# Page05_DDR4L_eMMC.net
KiCad netlist of a schematic drawn in Altium Designer
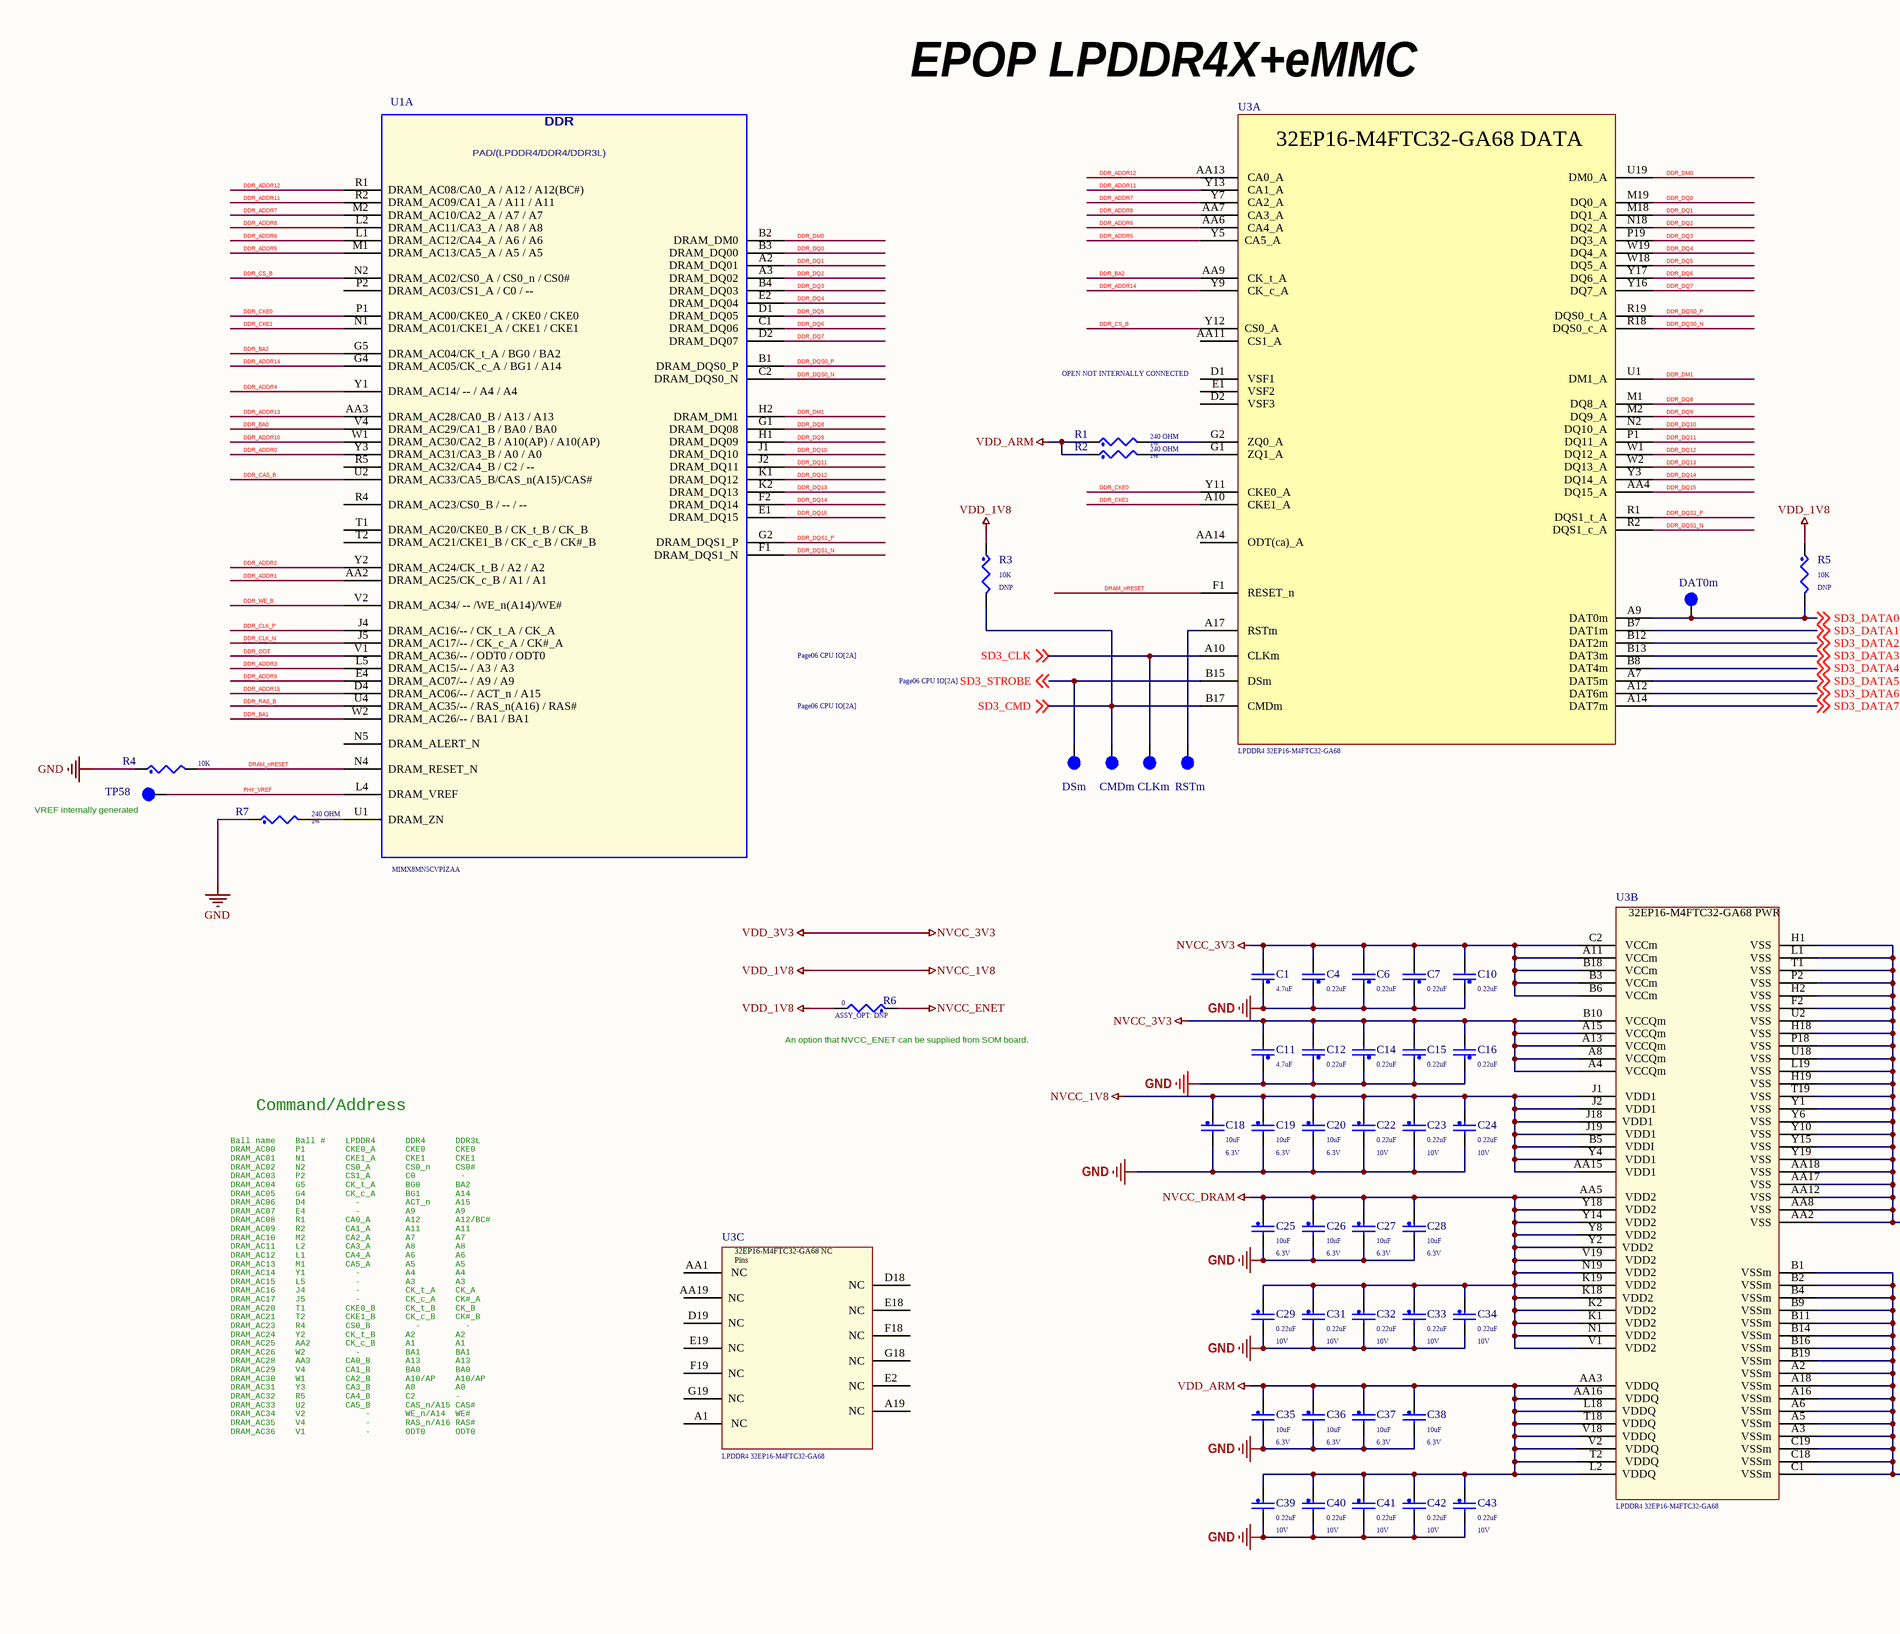
[diagram p0: Page05 DDR4L+eMMC.SchDoc, left]
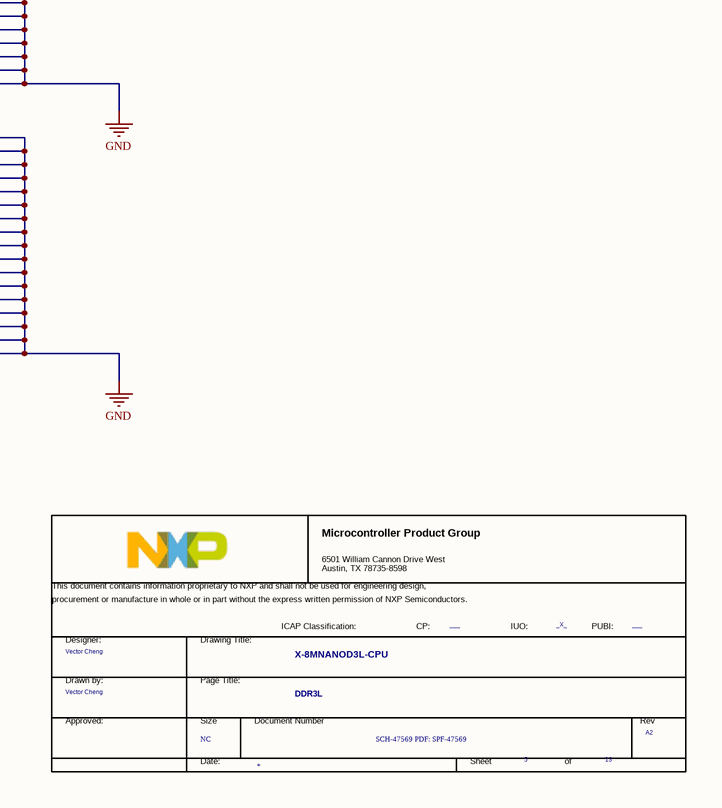
[diagram p1: Page05 DDR4L+eMMC.SchDoc, right]

(export (version "E")
  (design (tool "Eeschema 10.0.6"))
  (components
    (comp (ref "*")
      (value "TitleBlock_MCPG")
      (fields
        (field (name "FCP") "___")
        (field (name "FIUO") "_X_")
        (field (name "PUBI") "___")
        (field (name "DRAWNBY") "Vector Cheng")
        (field (name "DESIGNER") "Vector Cheng")
        (field (name "PAGETITLE") "DDR3L")
        (field (name "PAGE COUNT") "13")
        (field (name "PAGE NUMBER") "5")
        (field (name "PAGE SIZE") "NC")
        (field (name "TITLE") "X-8MNANOD3L-CPU")
        (field (name "REVCODE") "A2")
        (field (name "DOC") "SCH-47569 PDF: SPF-47569")
      )
      (libsource (lib "*") (part "TitleBlock_MCPG"))
    )
    (comp (ref "C1") (value "4.7uF") (footprint "0402_CC - C") (libsource (lib "AA_iMX8_M_") (part "CAP_NP")))
    (comp (ref "C4")
      (value "0.22uF")
      (footprint "0201_CC - C")
      (libsource (lib "AA_iMX8_M_") (part "CAP_NP"))
    )
    (comp (ref "C6")
      (value "0.22uF")
      (footprint "0201_CC - C")
      (libsource (lib "AA_iMX8_M_") (part "CAP_NP"))
    )
    (comp (ref "C7")
      (value "0.22uF")
      (footprint "0201_CC - C")
      (libsource (lib "AA_iMX8_M_") (part "CAP_NP"))
    )
    (comp (ref "C10")
      (value "0.22uF")
      (footprint "0201_CC - C")
      (libsource (lib "AA_iMX8_M_") (part "CAP_NP"))
    )
    (comp (ref "C11")
      (value "4.7uF")
      (footprint "0402_CC - C")
      (libsource (lib "AA_iMX8_M_") (part "CAP_NP"))
    )
    (comp (ref "C12")
      (value "0.22uF")
      (footprint "0201_CC - C")
      (libsource (lib "AA_iMX8_M_") (part "CAP_NP"))
    )
    (comp (ref "C14")
      (value "0.22uF")
      (footprint "0201_CC - C")
      (libsource (lib "AA_iMX8_M_") (part "CAP_NP"))
    )
    (comp (ref "C15")
      (value "0.22uF")
      (footprint "0201_CC - C")
      (libsource (lib "AA_iMX8_M_") (part "CAP_NP"))
    )
    (comp (ref "C16")
      (value "0.22uF")
      (footprint "0201_CC - C")
      (libsource (lib "AA_iMX8_M_") (part "CAP_NP"))
    )
    (comp (ref "C18")
      (value "10uF")
      (footprint "0402_CC - C")
      (fields (field (name "VOLTAGE") "6.3V"))
      (libsource (lib "AA_iMX8_M_") (part "CAP_NP"))
    )
    (comp (ref "C19")
      (value "10uF")
      (footprint "0402_CC - C")
      (fields (field (name "VOLTAGE") "6.3V"))
      (libsource (lib "AA_iMX8_M_") (part "CAP_NP"))
    )
    (comp (ref "C20")
      (value "10uF")
      (footprint "0402_CC - C")
      (fields (field (name "VOLTAGE") "6.3V"))
      (libsource (lib "AA_iMX8_M_") (part "CAP_NP"))
    )
    (comp (ref "C22")
      (value "0.22uF")
      (footprint "0201_CC - C")
      (fields (field (name "VOLTAGE") "10V"))
      (libsource (lib "AA_iMX8_M_") (part "CAP_NP"))
    )
    (comp (ref "C23")
      (value "0.22uF")
      (footprint "0201_CC - C")
      (fields (field (name "VOLTAGE") "10V"))
      (libsource (lib "AA_iMX8_M_") (part "CAP_NP"))
    )
    (comp (ref "C24")
      (value "0.22uF")
      (footprint "0201_CC - C")
      (fields (field (name "VOLTAGE") "10V"))
      (libsource (lib "AA_iMX8_M_") (part "CAP_NP"))
    )
    (comp (ref "C25")
      (value "10uF")
      (footprint "0402_CC - C")
      (fields (field (name "VOLTAGE") "6.3V"))
      (libsource (lib "AA_iMX8_M_") (part "CAP_NP"))
    )
    (comp (ref "C26")
      (value "10uF")
      (footprint "0402_CC - C")
      (fields (field (name "VOLTAGE") "6.3V"))
      (libsource (lib "AA_iMX8_M_") (part "CAP_NP"))
    )
    (comp (ref "C27")
      (value "10uF")
      (footprint "0402_CC - C")
      (fields (field (name "VOLTAGE") "6.3V"))
      (libsource (lib "AA_iMX8_M_") (part "CAP_NP"))
    )
    (comp (ref "C28")
      (value "10uF")
      (footprint "0402_CC - C")
      (fields (field (name "VOLTAGE") "6.3V"))
      (libsource (lib "AA_iMX8_M_") (part "CAP_NP"))
    )
    (comp (ref "C29")
      (value "0.22uF")
      (footprint "0201_CC - C")
      (fields (field (name "VOLTAGE") "10V"))
      (libsource (lib "AA_iMX8_M_") (part "CAP_NP"))
    )
    (comp (ref "C31")
      (value "0.22uF")
      (footprint "0201_CC - C")
      (fields (field (name "VOLTAGE") "10V"))
      (libsource (lib "AA_iMX8_M_") (part "CAP_NP"))
    )
    (comp (ref "C32")
      (value "0.22uF")
      (footprint "0201_CC - C")
      (fields (field (name "VOLTAGE") "10V"))
      (libsource (lib "AA_iMX8_M_") (part "CAP_NP"))
    )
    (comp (ref "C33")
      (value "0.22uF")
      (footprint "0201_CC - C")
      (fields (field (name "VOLTAGE") "10V"))
      (libsource (lib "AA_iMX8_M_") (part "CAP_NP"))
    )
    (comp (ref "C34")
      (value "0.22uF")
      (footprint "0201_CC - C")
      (fields (field (name "VOLTAGE") "10V"))
      (libsource (lib "AA_iMX8_M_") (part "CAP_NP"))
    )
    (comp (ref "C35")
      (value "10uF")
      (footprint "0402_CC - C")
      (fields (field (name "VOLTAGE") "6.3V"))
      (libsource (lib "AA_iMX8_M_") (part "CAP_NP"))
    )
    (comp (ref "C36")
      (value "10uF")
      (footprint "0402_CC - C")
      (fields (field (name "VOLTAGE") "6.3V"))
      (libsource (lib "AA_iMX8_M_") (part "CAP_NP"))
    )
    (comp (ref "C37")
      (value "10uF")
      (footprint "0402_CC - C")
      (fields (field (name "VOLTAGE") "6.3V"))
      (libsource (lib "AA_iMX8_M_") (part "CAP_NP"))
    )
    (comp (ref "C38")
      (value "10uF")
      (footprint "0402_CC - C")
      (fields (field (name "VOLTAGE") "6.3V"))
      (libsource (lib "AA_iMX8_M_") (part "CAP_NP"))
    )
    (comp (ref "C39")
      (value "0.22uF")
      (footprint "0201_CC - C")
      (fields (field (name "VOLTAGE") "10V"))
      (libsource (lib "AA_iMX8_M_") (part "CAP_NP"))
    )
    (comp (ref "C40")
      (value "0.22uF")
      (footprint "0201_CC - C")
      (fields (field (name "VOLTAGE") "10V"))
      (libsource (lib "AA_iMX8_M_") (part "CAP_NP"))
    )
    (comp (ref "C41")
      (value "0.22uF")
      (footprint "0201_CC - C")
      (fields (field (name "VOLTAGE") "10V"))
      (libsource (lib "AA_iMX8_M_") (part "CAP_NP"))
    )
    (comp (ref "C42")
      (value "0.22uF")
      (footprint "0201_CC - C")
      (fields (field (name "VOLTAGE") "10V"))
      (libsource (lib "AA_iMX8_M_") (part "CAP_NP"))
    )
    (comp (ref "C43")
      (value "0.22uF")
      (footprint "0201_CC - C")
      (fields (field (name "VOLTAGE") "10V"))
      (libsource (lib "AA_iMX8_M_") (part "CAP_NP"))
    )
    (comp (ref "CLKm")
      (value "tpad_020")
      (footprint "Test Pin")
      (description "TEST POINT PAD 0.5MM DIA SMT, NO PART TO ORDER")
      (libsource (lib "*") (part "TESTLOOP"))
    )
    (comp (ref "CMDm")
      (value "TPAD_015")
      (footprint "Test Pin")
      (description "TEST POINT PAD 15MIL DIA SMT, NO PART TO ORDER")
      (libsource (lib "*") (part "TESTLOOP"))
    )
    (comp (ref "DAT0m")
      (value "tpad_020")
      (footprint "Test Pin")
      (description "TEST POINT PAD 0.5MM DIA SMT, NO PART TO ORDER")
      (libsource (lib "*") (part "TESTLOOP"))
    )
    (comp (ref "DSm")
      (value "TPAD_015")
      (footprint "Test Pin")
      (description "TEST POINT PAD 15MIL DIA SMT, NO PART TO ORDER")
      (libsource (lib "*") (part "TESTLOOP"))
    )
    (comp (ref "R1")
      (value "240 OHM")
      (footprint "0201_RES")
      (description "RES MF 240 OHM 1/20W 1% 0201")
      (fields (field (name "VOLTAGE") "25V") (field (name "TOLERANCE") "1%"))
      (libsource (lib "*") (part "RES"))
    )
    (comp (ref "R2")
      (value "240 OHM")
      (footprint "0201_RES")
      (description "RES MF 240 OHM 1/20W 1% 0201")
      (fields (field (name "VOLTAGE") "25V") (field (name "TOLERANCE") "1%"))
      (libsource (lib "*") (part "RES"))
    )
    (comp (ref "R3")
      (value "10K")
      (footprint "0201_RES")
      (description "RES MF 10K 1/20W 5% 0201")
      (fields (field (name "ASSY_OPT") "DNP") (field (name "TOLERANCE") "5%"))
      (libsource (lib "*") (part "RES"))
    )
    (comp (ref "R4")
      (value "10K")
      (footprint "0201_RES")
      (description "RES MF 10K 1/20W 5% 0201")
      (fields (field (name "TOLERANCE") "5%"))
      (libsource (lib "*") (part "RES"))
    )
    (comp (ref "R5")
      (value "10K")
      (footprint "0201_RES")
      (description "RES MF 10K 1/20W 5% 0201")
      (fields (field (name "ASSY_OPT") "DNP") (field (name "TOLERANCE") "5%"))
      (libsource (lib "*") (part "RES"))
    )
    (comp (ref "R6")
      (value "0")
      (footprint "0402_CC_RES")
      (description "RES MF ZERO OHM 1/16W 5% 0402")
      (fields
        (field (name "ASSY_OPT") "DNP")
        (field (name "TOLERANCE") "5%")
        (field (name "VOLTAGE") "1/16W")
      )
      (libsource (lib "*") (part "RES"))
    )
    (comp (ref "R7")
      (value "240 OHM")
      (footprint "0201_RES")
      (description "RES MF 240 OHM 1/20W 1% 0201")
      (fields (field (name "VOLTAGE") "25V") (field (name "TOLERANCE") "1%"))
      (libsource (lib "*") (part "RES"))
    )
    (comp (ref "RSTm")
      (value "tpad_020")
      (footprint "Test Pin")
      (description "TEST POINT PAD 0.5MM DIA SMT, NO PART TO ORDER")
      (libsource (lib "*") (part "TESTLOOP"))
    )
    (comp (ref "TP58")
      (value "tpad_020")
      (footprint "Test Pin")
      (description "TEST POINT PAD 0.5MM DIA SMT, NO PART TO ORDER")
      (libsource (lib "*") (part "TESTLOOP"))
    )
    (comp (ref "U1")
      (value "MIMX8MN5CVPIZAA")
      (footprint "BGA306C50P21X21_1100X1100X101")
      (description "IC CPU QUAD CORTEX A53+M7 1.4GHZ -- BGA306")
      (libsource (lib "*") (part "MIMX8MN"))
    )
    (comp (ref "U3")
      (value "LPDDR4 32EP16-M4FTC32-GA68")
      (footprint "FBGA144C40P19X21_800X950X80")
      (libsource (lib "Altium starter project NANO") (part "LPDDR4 32EP16-M4FTC32-GA68"))
    )
  )
  (nets
    (net (code "1") (name "/DDR_ADDR0") (class "Default")
      (node (ref "U1") (pin "Y3") (pinfunction "DRAM_AC31/CA3_B_/_A0_/_A0_Y3") (pintype "passive"))
    )
    (net (code "2") (name "/DDR_ADDR1") (class "Default")
      (node (ref "U1") (pin "AA2") (pinfunction "DRAM_AC25/CK_c_B_/_A1_/_A1_AA2") (pintype "passive"))
    )
    (net (code "3") (name "/DDR_ADDR2") (class "Default")
      (node (ref "U1") (pin "Y2") (pinfunction "DRAM_AC24/CK_t_B_/_A2_/_A2_Y2") (pintype "passive"))
    )
    (net (code "4") (name "/DDR_ADDR3") (class "Default")
      (node (ref "U1") (pin "L5") (pinfunction "DRAM_AC15/--_/_A3_/_A3_L5") (pintype "passive"))
    )
    (net (code "5") (name "/DDR_ADDR4") (class "Default")
      (node (ref "U1") (pin "Y1") (pinfunction "DRAM_AC14/_--_/_A4_/_A4_Y1") (pintype "passive"))
    )
    (net (code "6") (name "/DDR_ADDR5") (class "Default")
      (node (ref "U1") (pin "M1") (pinfunction "DRAM_AC13/CA5_A_/_A5_/_A5_M1") (pintype "passive"))
      (node (ref "U3") (pin "Y5") (pinfunction "CA5_A_Y5") (pintype "passive"))
    )
    (net (code "7") (name "/DDR_ADDR6") (class "Default")
      (node (ref "U1") (pin "L1") (pinfunction "DRAM_AC12/CA4_A_/_A6_/_A6_L1") (pintype "passive"))
      (node (ref "U3") (pin "AA6") (pinfunction "_CA4_A_AA6") (pintype "passive"))
    )
    (net (code "8") (name "/DDR_ADDR7") (class "Default")
      (node (ref "U1") (pin "M2") (pinfunction "DRAM_AC10/CA2_A_/_A7_/_A7_M2") (pintype "passive"))
      (node (ref "U3") (pin "Y7") (pinfunction "_CA2_A_Y7") (pintype "passive"))
    )
    (net (code "9") (name "/DDR_ADDR8") (class "Default")
      (node (ref "U1") (pin "L2") (pinfunction "DRAM_AC11/CA3_A_/_A8_/_A8_L2") (pintype "passive"))
      (node (ref "U3") (pin "AA7") (pinfunction "_CA3_A_AA7") (pintype "passive"))
    )
    (net (code "10") (name "/DDR_ADDR9") (class "Default")
      (node (ref "U1") (pin "E4") (pinfunction "DRAM_AC07/--_/_A9_/_A9_E4") (pintype "passive"))
    )
    (net (code "11") (name "/DDR_ADDR10") (class "Default")
      (node (ref "U1") (pin "W1") (pinfunction "DRAM_AC30/CA2_B_/_A10(AP)_/_A10(AP)_W1") (pintype "passive"))
    )
    (net (code "12") (name "/DDR_ADDR11") (class "Default")
      (node (ref "U1") (pin "R2") (pinfunction "DRAM_AC09/CA1_A_/_A11_/_A11_R2") (pintype "passive"))
      (node (ref "U3") (pin "Y13") (pinfunction "_CA1_A_Y13") (pintype "passive"))
    )
    (net (code "13") (name "/DDR_ADDR12") (class "Default")
      (node (ref "U1") (pin "R1") (pinfunction "DRAM_AC08/CA0_A_/_A12_/_A12(BC#)_R1") (pintype "passive"))
      (node (ref "U3") (pin "AA13") (pinfunction "_CA0_A_AA13") (pintype "passive"))
    )
    (net (code "14") (name "/DDR_ADDR13") (class "Default")
      (node (ref "U1") (pin "AA3") (pinfunction "DRAM_AC28/CA0_B_/_A13_/_A13_AA3") (pintype "passive"))
    )
    (net (code "15") (name "/DDR_ADDR14") (class "Default")
      (node (ref "U1") (pin "G4") (pinfunction "DRAM_AC05/CK_c_A_/_BG1_/_A14_G4") (pintype "passive"))
      (node (ref "U3") (pin "Y9") (pinfunction "_CK_c_A_Y9") (pintype "passive"))
    )
    (net (code "16") (name "/DDR_ADDR15") (class "Default")
      (node (ref "U1") (pin "D4") (pinfunction "DRAM_AC06/--_/_ACT_n_/_A15_D4") (pintype "passive"))
    )
    (net (code "17") (name "/DDR_BA0") (class "Default")
      (node (ref "U1") (pin "V4") (pinfunction "DRAM_AC29/CA1_B_/_BA0_/_BA0_V4") (pintype "passive"))
    )
    (net (code "18") (name "/DDR_BA1") (class "Default")
      (node (ref "U1") (pin "W2") (pinfunction "DRAM_AC26/--_/_BA1_/_BA1_W2") (pintype "passive"))
    )
    (net (code "19") (name "/DDR_BA2") (class "Default")
      (node (ref "U1") (pin "G5") (pinfunction "DRAM_AC04/CK_t_A_/_BG0_/_BA2_G5") (pintype "passive"))
      (node (ref "U3") (pin "AA9") (pinfunction "_CK_t_A_AA9") (pintype "passive"))
    )
    (net (code "20") (name "/DDR_CAS_B") (class "Default")
      (node (ref "U1") (pin "U2") (pinfunction "DRAM_AC33/CA5_B/CAS_n(A15)/CAS#_U2") (pintype "passive"))
    )
    (net (code "21") (name "/DDR_CKE0") (class "Default")
      (node (ref "U1") (pin "P1") (pinfunction "DRAM_AC00/CKE0_A_/_CKE0_/_CKE0_P1") (pintype "passive"))
      (node (ref "U3") (pin "Y11") (pinfunction "_CKE0_A_Y11") (pintype "passive"))
    )
    (net (code "22") (name "/DDR_CKE1") (class "Default")
      (node (ref "U1") (pin "N1") (pinfunction "DRAM_AC01/CKE1_A_/_CKE1_/_CKE1_N1") (pintype "passive"))
      (node (ref "U3") (pin "A10") (pinfunction "_CKE1_A_A10") (pintype "passive"))
    )
    (net (code "23") (name "/DDR_CLK_N") (class "Default")
      (node (ref "U1") (pin "J5") (pinfunction "DRAM_AC17/--_/_CK_c_A_/_CK#_A_J5") (pintype "passive"))
    )
    (net (code "24") (name "/DDR_CLK_P") (class "Default")
      (node (ref "U1") (pin "J4") (pinfunction "DRAM_AC16/--_/_CK_t_A_/_CK_A_J4") (pintype "passive"))
    )
    (net (code "25") (name "/DDR_CS_B") (class "Default")
      (node (ref "U1") (pin "N2") (pinfunction "DRAM_AC02/CS0_A_/_CS0_n_/_CS0#_N2") (pintype "passive"))
      (node (ref "U3") (pin "Y12") (pinfunction "CS0_A_Y12") (pintype "passive"))
    )
    (net (code "26") (name "/DDR_DM0") (class "Default")
      (node (ref "U1") (pin "B2") (pinfunction "DRAM_DM0_B2") (pintype "passive"))
      (node (ref "U3") (pin "U19") (pinfunction "_DM0_A_U19") (pintype "passive"))
    )
    (net (code "27") (name "/DDR_DM1") (class "Default")
      (node (ref "U1") (pin "H2") (pinfunction "DRAM_DM1_H2") (pintype "passive"))
      (node (ref "U3") (pin "U1") (pinfunction "_DM1_A_U1") (pintype "passive"))
    )
    (net (code "28") (name "/DDR_DQ0") (class "Default")
      (node (ref "U1") (pin "B3") (pinfunction "DRAM_DQ00_B3") (pintype "passive"))
      (node (ref "U3") (pin "M19") (pinfunction "_DQ0_A_M19") (pintype "passive"))
    )
    (net (code "29") (name "/DDR_DQ1") (class "Default")
      (node (ref "U1") (pin "A2") (pinfunction "DRAM_DQ01_A2") (pintype "passive"))
      (node (ref "U3") (pin "M18") (pinfunction "DQ1_A_M18") (pintype "passive"))
    )
    (net (code "30") (name "/DDR_DQ2") (class "Default")
      (node (ref "U1") (pin "A3") (pinfunction "DRAM_DQ02_A3") (pintype "passive"))
      (node (ref "U3") (pin "N18") (pinfunction "DQ2_A_N18") (pintype "passive"))
    )
    (net (code "31") (name "/DDR_DQ3") (class "Default")
      (node (ref "U1") (pin "B4") (pinfunction "DRAM_DQ03_B4") (pintype "passive"))
      (node (ref "U3") (pin "P19") (pinfunction "DQ3_A_P19") (pintype "passive"))
    )
    (net (code "32") (name "/DDR_DQ4") (class "Default")
      (node (ref "U1") (pin "E2") (pinfunction "DRAM_DQ04_E2") (pintype "passive"))
      (node (ref "U3") (pin "W19") (pinfunction "_DQ4_A_W19") (pintype "passive"))
    )
    (net (code "33") (name "/DDR_DQ5") (class "Default")
      (node (ref "U1") (pin "D1") (pinfunction "DRAM_DQ05_D1") (pintype "passive"))
      (node (ref "U3") (pin "W18") (pinfunction "DQ5_A_W18") (pintype "passive"))
    )
    (net (code "34") (name "/DDR_DQ6") (class "Default")
      (node (ref "U1") (pin "C1") (pinfunction "DRAM_DQ06_C1") (pintype "passive"))
      (node (ref "U3") (pin "Y17") (pinfunction "_DQ6_A_Y17") (pintype "passive"))
    )
    (net (code "35") (name "/DDR_DQ7") (class "Default")
      (node (ref "U1") (pin "D2") (pinfunction "DRAM_DQ07_D2") (pintype "passive"))
      (node (ref "U3") (pin "Y16") (pinfunction "_DQ7_A_Y16") (pintype "passive"))
    )
    (net (code "36") (name "/DDR_DQ8") (class "Default")
      (node (ref "U1") (pin "G1") (pinfunction "DRAM_DQ08_G1") (pintype "passive"))
      (node (ref "U3") (pin "M1") (pinfunction "_DQ8_A_M1") (pintype "passive"))
    )
    (net (code "37") (name "/DDR_DQ9") (class "Default")
      (node (ref "U1") (pin "H1") (pinfunction "DRAM_DQ09_H1") (pintype "passive"))
      (node (ref "U3") (pin "M2") (pinfunction "_DQ9_A_M2") (pintype "passive"))
    )
    (net (code "38") (name "/DDR_DQ10") (class "Default")
      (node (ref "U1") (pin "J1") (pinfunction "DRAM_DQ10_J1") (pintype "passive"))
      (node (ref "U3") (pin "N2") (pinfunction "_DQ10_A_N2") (pintype "passive"))
    )
    (net (code "39") (name "/DDR_DQ11") (class "Default")
      (node (ref "U1") (pin "J2") (pinfunction "DRAM_DQ11_J2") (pintype "passive"))
      (node (ref "U3") (pin "P1") (pinfunction "_DQ11_A_P1") (pintype "passive"))
    )
    (net (code "40") (name "/DDR_DQ12") (class "Default")
      (node (ref "U1") (pin "K1") (pinfunction "DRAM_DQ12_K1") (pintype "passive"))
      (node (ref "U3") (pin "W1") (pinfunction "_DQ12_A_W1") (pintype "passive"))
    )
    (net (code "41") (name "/DDR_DQ13") (class "Default")
      (node (ref "U1") (pin "K2") (pinfunction "DRAM_DQ13_K2") (pintype "passive"))
      (node (ref "U3") (pin "W2") (pinfunction "_DQ13_A_W2") (pintype "passive"))
    )
    (net (code "42") (name "/DDR_DQ14") (class "Default")
      (node (ref "U1") (pin "F2") (pinfunction "DRAM_DQ14_F2") (pintype "passive"))
      (node (ref "U3") (pin "Y3") (pinfunction "_DQ14_A_Y3") (pintype "passive"))
    )
    (net (code "43") (name "/DDR_DQ15") (class "Default")
      (node (ref "U1") (pin "E1") (pinfunction "DRAM_DQ15_E1") (pintype "passive"))
      (node (ref "U3") (pin "AA4") (pinfunction "_DQ15_A_AA4") (pintype "passive"))
    )
    (net (code "44") (name "/DDR_DQS0_N") (class "Default")
      (node (ref "U1") (pin "C2") (pinfunction "DRAM_DQS0_N_C2") (pintype "passive"))
      (node (ref "U3") (pin "R18") (pinfunction "DQS0_c_A_R18") (pintype "passive"))
    )
    (net (code "45") (name "/DDR_DQS0_P") (class "Default")
      (node (ref "U1") (pin "B1") (pinfunction "DRAM_DQS0_P_B1") (pintype "passive"))
      (node (ref "U3") (pin "R19") (pinfunction "_DQS0_t_A_R19") (pintype "passive"))
    )
    (net (code "46") (name "/DDR_DQS1_N") (class "Default")
      (node (ref "U1") (pin "F1") (pinfunction "DRAM_DQS1_N_F1") (pintype "passive"))
      (node (ref "U3") (pin "R2") (pinfunction "_DQS1_c_A_R2") (pintype "passive"))
    )
    (net (code "47") (name "/DDR_DQS1_P") (class "Default")
      (node (ref "U1") (pin "G2") (pinfunction "DRAM_DQS1_P_G2") (pintype "passive"))
      (node (ref "U3") (pin "R1") (pinfunction "_DQS1_t_A_R1") (pintype "passive"))
    )
    (net (code "48") (name "/DDR_ODT") (class "Default")
      (node (ref "U1") (pin "V1") (pinfunction "DRAM_AC36/--_/_ODT0_/_ODT0_V1") (pintype "passive"))
    )
    (net (code "49") (name "/DDR_RAS_B") (class "Default")
      (node (ref "U1") (pin "U4") (pinfunction "DRAM_AC35/--_/_RAS_n(A16)_/_RAS#_U4") (pintype "passive"))
    )
    (net (code "50") (name "/DDR_WE_B") (class "Default")
      (node (ref "U1") (pin "V2") (pinfunction "DRAM_AC34/_--_/WE_n(A14)/WE#_V2") (pintype "passive"))
    )
    (net (code "51") (name "/DRAM_nRESET") (class "Default")
      (node (ref "R4") (pin "2") (pinfunction "2_2") (pintype "passive"))
      (node (ref "U1") (pin "N4") (pinfunction "DRAM_RESET_N_N4") (pintype "passive"))
      (node (ref "U3") (pin "F1") (pinfunction "_RESET_n_F1") (pintype "passive"))
    )
    (net (code "52") (name "/PHY_VREF") (class "Default")
      (node (ref "TP58") (pin "1") (pinfunction "Pin1_1") (pintype "passive"))
      (node (ref "U1") (pin "L4") (pinfunction "DRAM_VREF_L4") (pintype "passive"))
    )
    (net (code "53") (name "GND") (class "Default")
      (node (ref "C1") (pin "1") (pinfunction "1_1") (pintype "passive"))
      (node (ref "C10") (pin "1") (pinfunction "1_1") (pintype "passive"))
      (node (ref "C11") (pin "1") (pinfunction "1_1") (pintype "passive"))
      (node (ref "C12") (pin "1") (pinfunction "1_1") (pintype "passive"))
      (node (ref "C14") (pin "1") (pinfunction "1_1") (pintype "passive"))
      (node (ref "C15") (pin "1") (pinfunction "1_1") (pintype "passive"))
      (node (ref "C16") (pin "1") (pinfunction "1_1") (pintype "passive"))
      (node (ref "C18") (pin "2") (pinfunction "2_2") (pintype "passive"))
      (node (ref "C19") (pin "2") (pinfunction "2_2") (pintype "passive"))
      (node (ref "C20") (pin "2") (pinfunction "2_2") (pintype "passive"))
      (node (ref "C22") (pin "2") (pinfunction "2_2") (pintype "passive"))
      (node (ref "C23") (pin "2") (pinfunction "2_2") (pintype "passive"))
      (node (ref "C24") (pin "2") (pinfunction "2_2") (pintype "passive"))
      (node (ref "C25") (pin "2") (pinfunction "2_2") (pintype "passive"))
      (node (ref "C26") (pin "2") (pinfunction "2_2") (pintype "passive"))
      (node (ref "C27") (pin "2") (pinfunction "2_2") (pintype "passive"))
      (node (ref "C28") (pin "2") (pinfunction "2_2") (pintype "passive"))
      (node (ref "C29") (pin "2") (pinfunction "2_2") (pintype "passive"))
      (node (ref "C31") (pin "2") (pinfunction "2_2") (pintype "passive"))
      (node (ref "C32") (pin "2") (pinfunction "2_2") (pintype "passive"))
      (node (ref "C33") (pin "2") (pinfunction "2_2") (pintype "passive"))
      (node (ref "C34") (pin "2") (pinfunction "2_2") (pintype "passive"))
      (node (ref "C35") (pin "2") (pinfunction "2_2") (pintype "passive"))
      (node (ref "C36") (pin "2") (pinfunction "2_2") (pintype "passive"))
      (node (ref "C37") (pin "2") (pinfunction "2_2") (pintype "passive"))
      (node (ref "C38") (pin "2") (pinfunction "2_2") (pintype "passive"))
      (node (ref "C39") (pin "2") (pinfunction "2_2") (pintype "passive"))
      (node (ref "C4") (pin "1") (pinfunction "1_1") (pintype "passive"))
      (node (ref "C40") (pin "2") (pinfunction "2_2") (pintype "passive"))
      (node (ref "C41") (pin "2") (pinfunction "2_2") (pintype "passive"))
      (node (ref "C42") (pin "2") (pinfunction "2_2") (pintype "passive"))
      (node (ref "C43") (pin "2") (pinfunction "2_2") (pintype "passive"))
      (node (ref "C6") (pin "1") (pinfunction "1_1") (pintype "passive"))
      (node (ref "C7") (pin "1") (pinfunction "1_1") (pintype "passive"))
      (node (ref "R4") (pin "1") (pinfunction "1_1") (pintype "passive"))
      (node (ref "R7") (pin "1") (pinfunction "1_1") (pintype "passive"))
      (node (ref "U3") (pin "A16") (pinfunction "_VSSm_A16") (pintype "power_in"))
      (node (ref "U3") (pin "A18") (pinfunction "_VSSm_A18") (pintype "power_in"))
      (node (ref "U3") (pin "A2") (pinfunction "_VSSm_A2") (pintype "power_in"))
      (node (ref "U3") (pin "A3") (pinfunction "VSSm_A3") (pintype "power_in"))
      (node (ref "U3") (pin "A5") (pinfunction "_VSSm_A5") (pintype "power_in"))
      (node (ref "U3") (pin "A6") (pinfunction "_VSSm_A6") (pintype "power_in"))
      (node (ref "U3") (pin "AA12") (pinfunction "_VSS_AA12") (pintype "power_in"))
      (node (ref "U3") (pin "AA17") (pinfunction "_VSS_AA17") (pintype "power_in"))
      (node (ref "U3") (pin "AA18") (pinfunction "VSS_AA18") (pintype "power_in"))
      (node (ref "U3") (pin "AA2") (pinfunction "VSS_AA2") (pintype "power_in"))
      (node (ref "U3") (pin "AA8") (pinfunction "_VSS_AA8") (pintype "power_in"))
      (node (ref "U3") (pin "B1") (pinfunction "_VSSm_B1") (pintype "power_in"))
      (node (ref "U3") (pin "B11") (pinfunction "_VSSm_B11") (pintype "power_in"))
      (node (ref "U3") (pin "B14") (pinfunction "_VSSm_B14") (pintype "power_in"))
      (node (ref "U3") (pin "B16") (pinfunction "_VSSm_B16") (pintype "power_in"))
      (node (ref "U3") (pin "B19") (pinfunction "_VSSm_B19") (pintype "power_in"))
      (node (ref "U3") (pin "B2") (pinfunction "_VSSm_B2") (pintype "power_in"))
      (node (ref "U3") (pin "B4") (pinfunction "_VSSm_B4") (pintype "power_in"))
      (node (ref "U3") (pin "B9") (pinfunction "_VSSm_B9") (pintype "power_in"))
      (node (ref "U3") (pin "C1") (pinfunction "_VSSm_C1") (pintype "power_in"))
      (node (ref "U3") (pin "C18") (pinfunction "VSSm_C18") (pintype "power_in"))
      (node (ref "U3") (pin "C19") (pinfunction "_VSSm_C19") (pintype "power_in"))
      (node (ref "U3") (pin "F2") (pinfunction "_VSS_F2") (pintype "power_in"))
      (node (ref "U3") (pin "H1") (pinfunction "_VSS_H1") (pintype "power_in"))
      (node (ref "U3") (pin "H18") (pinfunction "VSS_H18") (pintype "power_in"))
      (node (ref "U3") (pin "H19") (pinfunction "VSS_H19") (pintype "power_in"))
      (node (ref "U3") (pin "H2") (pinfunction "VSS_H2") (pintype "power_in"))
      (node (ref "U3") (pin "L1") (pinfunction "_VSS_L1") (pintype "power_in"))
      (node (ref "U3") (pin "L19") (pinfunction "VSS_L19") (pintype "power_in"))
      (node (ref "U3") (pin "P18") (pinfunction "VSS_P18") (pintype "power_in"))
      (node (ref "U3") (pin "P2") (pinfunction "_VSS_P2") (pintype "power_in"))
      (node (ref "U3") (pin "T1") (pinfunction "_VSS_T1") (pintype "power_in"))
      (node (ref "U3") (pin "T19") (pinfunction "VSS_T19") (pintype "power_in"))
      (node (ref "U3") (pin "U18") (pinfunction "VSS_U18") (pintype "power_in"))
      (node (ref "U3") (pin "U2") (pinfunction "_VSS_U2") (pintype "power_in"))
      (node (ref "U3") (pin "Y1") (pinfunction "_VSS_Y1") (pintype "power_in"))
      (node (ref "U3") (pin "Y10") (pinfunction "_VSS_Y10") (pintype "power_in"))
      (node (ref "U3") (pin "Y15") (pinfunction "_VSS_Y15") (pintype "power_in"))
      (node (ref "U3") (pin "Y19") (pinfunction "VSS_Y19") (pintype "power_in"))
      (node (ref "U3") (pin "Y6") (pinfunction "_VSS_Y6") (pintype "power_in"))
    )
    (net (code "54") (name "NVCC_1V8") (class "Default")
      (node (ref "C18") (pin "1") (pinfunction "1_1") (pintype "passive"))
      (node (ref "C19") (pin "1") (pinfunction "1_1") (pintype "passive"))
      (node (ref "C20") (pin "1") (pinfunction "1_1") (pintype "passive"))
      (node (ref "C22") (pin "1") (pinfunction "1_1") (pintype "passive"))
      (node (ref "C23") (pin "1") (pinfunction "1_1") (pintype "passive"))
      (node (ref "C24") (pin "1") (pinfunction "1_1") (pintype "passive"))
      (node (ref "R3") (pin "1") (pinfunction "1_1") (pintype "passive"))
      (node (ref "R5") (pin "1") (pinfunction "1_1") (pintype "passive"))
      (node (ref "R6") (pin "2") (pinfunction "2_2") (pintype "passive"))
      (node (ref "U3") (pin "AA15") (pinfunction "_VDD1_AA15") (pintype "power_in"))
      (node (ref "U3") (pin "B5") (pinfunction "_VDDI_B5") (pintype "power_in"))
      (node (ref "U3") (pin "J1") (pinfunction "_VDD1_J1") (pintype "power_in"))
      (node (ref "U3") (pin "J18") (pinfunction "VDD1_J18") (pintype "power_in"))
      (node (ref "U3") (pin "J19") (pinfunction "_VDD1_J19") (pintype "power_in"))
      (node (ref "U3") (pin "J2") (pinfunction "_VDD1_J2") (pintype "power_in"))
      (node (ref "U3") (pin "Y4") (pinfunction "_VDD1_Y4") (pintype "power_in"))
    )
    (net (code "55") (name "NVCC_3V3") (class "Default")
      (node (ref "C1") (pin "2") (pinfunction "2_2") (pintype "passive"))
      (node (ref "C10") (pin "2") (pinfunction "2_2") (pintype "passive"))
      (node (ref "C11") (pin "2") (pinfunction "2_2") (pintype "passive"))
      (node (ref "C12") (pin "2") (pinfunction "2_2") (pintype "passive"))
      (node (ref "C14") (pin "2") (pinfunction "2_2") (pintype "passive"))
      (node (ref "C15") (pin "2") (pinfunction "2_2") (pintype "passive"))
      (node (ref "C16") (pin "2") (pinfunction "2_2") (pintype "passive"))
      (node (ref "C4") (pin "2") (pinfunction "2_2") (pintype "passive"))
      (node (ref "C6") (pin "2") (pinfunction "2_2") (pintype "passive"))
      (node (ref "C7") (pin "2") (pinfunction "2_2") (pintype "passive"))
      (node (ref "U3") (pin "A11") (pinfunction "_VCCm_A11") (pintype "power_in"))
      (node (ref "U3") (pin "A13") (pinfunction "_VCCQm_A13") (pintype "power_in"))
      (node (ref "U3") (pin "A15") (pinfunction "_VCCQm_A15") (pintype "power_in"))
      (node (ref "U3") (pin "A4") (pinfunction "_VCCQm_A4") (pintype "power_in"))
      (node (ref "U3") (pin "A8") (pinfunction "_VCCQm_A8") (pintype "power_in"))
      (node (ref "U3") (pin "B10") (pinfunction "_VCCQm_B10") (pintype "power_in"))
      (node (ref "U3") (pin "B18") (pinfunction "_VCCm_B18") (pintype "power_in"))
      (node (ref "U3") (pin "B3") (pinfunction "_VCCm_B3") (pintype "power_in"))
      (node (ref "U3") (pin "B6") (pinfunction "_VCCm_B6") (pintype "power_in"))
      (node (ref "U3") (pin "C2") (pinfunction "_VCCm_C2") (pintype "power_in"))
    )
    (net (code "56") (name "NVCC_DRAM") (class "Default")
      (node (ref "C25") (pin "1") (pinfunction "1_1") (pintype "passive"))
      (node (ref "C26") (pin "1") (pinfunction "1_1") (pintype "passive"))
      (node (ref "C27") (pin "1") (pinfunction "1_1") (pintype "passive"))
      (node (ref "C28") (pin "1") (pinfunction "1_1") (pintype "passive"))
      (node (ref "C29") (pin "1") (pinfunction "1_1") (pintype "passive"))
      (node (ref "C31") (pin "1") (pinfunction "1_1") (pintype "passive"))
      (node (ref "C32") (pin "1") (pinfunction "1_1") (pintype "passive"))
      (node (ref "C33") (pin "1") (pinfunction "1_1") (pintype "passive"))
      (node (ref "C34") (pin "1") (pinfunction "1_1") (pintype "passive"))
      (node (ref "U3") (pin "AA5") (pinfunction "_VDD2_AA5") (pintype "power_in"))
      (node (ref "U3") (pin "K1") (pinfunction "_VDD2_K1") (pintype "power_in"))
      (node (ref "U3") (pin "K18") (pinfunction "VDD2_K18") (pintype "power_in"))
      (node (ref "U3") (pin "K19") (pinfunction "_VDD2_K19") (pintype "power_in"))
      (node (ref "U3") (pin "K2") (pinfunction "_VDD2_K2") (pintype "power_in"))
      (node (ref "U3") (pin "N1") (pinfunction "_VDD2_N1") (pintype "power_in"))
      (node (ref "U3") (pin "N19") (pinfunction "_VDD2_N19") (pintype "power_in"))
      (node (ref "U3") (pin "V1") (pinfunction "_VDD2_V1") (pintype "power_in"))
      (node (ref "U3") (pin "V19") (pinfunction "_VDD2_V19") (pintype "power_in"))
      (node (ref "U3") (pin "Y14") (pinfunction "_VDD2_Y14") (pintype "power_in"))
      (node (ref "U3") (pin "Y18") (pinfunction "_VDD2_Y18") (pintype "power_in"))
      (node (ref "U3") (pin "Y2") (pinfunction "VDD2_Y2") (pintype "power_in"))
      (node (ref "U3") (pin "Y8") (pinfunction "_VDD2_Y8") (pintype "power_in"))
    )
    (net (code "57") (name "NVCC_ENET") (class "Default")
      (node (ref "R6") (pin "1") (pinfunction "1_1") (pintype "passive"))
    )
    (net (code "58") (name "Net-(RSTm-Pin1)") (class "Default")
      (node (ref "RSTm") (pin "1") (pinfunction "Pin1_1") (pintype "passive"))
      (node (ref "U3") (pin "A17") (pinfunction "_RSTm_A17") (pintype "passive"))
    )
    (net (code "59") (name "Net-(U1A-DRAM_ZN)") (class "Default")
      (node (ref "R7") (pin "2") (pinfunction "2_2") (pintype "passive"))
      (node (ref "U1") (pin "U1") (pinfunction "DRAM_ZN_U1") (pintype "passive"))
    )
    (net (code "60") (name "Net-(U3A-_ZQ0_A)") (class "Default")
      (node (ref "R1") (pin "2") (pinfunction "2_2") (pintype "passive"))
      (node (ref "U3") (pin "G2") (pinfunction "_ZQ0_A_G2") (pintype "passive"))
    )
    (net (code "61") (name "Net-(U3A-_ZQ1_A)") (class "Default")
      (node (ref "R2") (pin "2") (pinfunction "2_2") (pintype "passive"))
      (node (ref "U3") (pin "G1") (pinfunction "_ZQ1_A_G1") (pintype "passive"))
    )
    (net (code "62") (name "SD3_CLK") (class "Default")
      (node (ref "CLKm") (pin "1") (pinfunction "Pin1_1") (pintype "passive"))
      (node (ref "U3") (pin "A10") (pinfunction "_CLKm_A10") (pintype "passive"))
    )
    (net (code "63") (name "SD3_CMD") (class "Default")
      (node (ref "CMDm") (pin "1") (pinfunction "Pin1_1") (pintype "passive"))
      (node (ref "R3") (pin "2") (pinfunction "2_2") (pintype "passive"))
      (node (ref "U3") (pin "B17") (pinfunction "_CMDm_B17") (pintype "passive"))
    )
    (net (code "64") (name "SD3_DATA0") (class "Default")
      (node (ref "DAT0m") (pin "1") (pinfunction "Pin1_1") (pintype "passive"))
      (node (ref "R5") (pin "2") (pinfunction "2_2") (pintype "passive"))
      (node (ref "U3") (pin "A9") (pinfunction "_DAT0m_A9") (pintype "passive"))
    )
    (net (code "65") (name "SD3_DATA1") (class "Default")
      (node (ref "U3") (pin "B7") (pinfunction "DAT1m_B7") (pintype "passive"))
    )
    (net (code "66") (name "SD3_DATA2") (class "Default")
      (node (ref "U3") (pin "B12") (pinfunction "_DAT2m_B12") (pintype "passive"))
    )
    (net (code "67") (name "SD3_DATA3") (class "Default")
      (node (ref "U3") (pin "B13") (pinfunction "_DAT3m_B13") (pintype "passive"))
    )
    (net (code "68") (name "SD3_DATA4") (class "Default")
      (node (ref "U3") (pin "B8") (pinfunction "_DAT4m_B8") (pintype "passive"))
    )
    (net (code "69") (name "SD3_DATA5") (class "Default")
      (node (ref "U3") (pin "A7") (pinfunction "_DAT5m_A7") (pintype "passive"))
    )
    (net (code "70") (name "SD3_DATA6") (class "Default")
      (node (ref "U3") (pin "A12") (pinfunction "_DAT6m_A12") (pintype "passive"))
    )
    (net (code "71") (name "SD3_DATA7") (class "Default")
      (node (ref "U3") (pin "A14") (pinfunction "_DAT7m_A14") (pintype "passive"))
    )
    (net (code "72") (name "SD3_STROBE") (class "Default")
      (node (ref "DSm") (pin "1") (pinfunction "Pin1_1") (pintype "passive"))
      (node (ref "U3") (pin "B15") (pinfunction "_DSm_B15") (pintype "passive"))
    )
    (net (code "73") (name "VDD_ARM") (class "Default")
      (node (ref "C35") (pin "1") (pinfunction "1_1") (pintype "passive"))
      (node (ref "C36") (pin "1") (pinfunction "1_1") (pintype "passive"))
      (node (ref "C37") (pin "1") (pinfunction "1_1") (pintype "passive"))
      (node (ref "C38") (pin "1") (pinfunction "1_1") (pintype "passive"))
      (node (ref "C39") (pin "1") (pinfunction "1_1") (pintype "passive"))
      (node (ref "C40") (pin "1") (pinfunction "1_1") (pintype "passive"))
      (node (ref "C41") (pin "1") (pinfunction "1_1") (pintype "passive"))
      (node (ref "C42") (pin "1") (pinfunction "1_1") (pintype "passive"))
      (node (ref "C43") (pin "1") (pinfunction "1_1") (pintype "passive"))
      (node (ref "R1") (pin "1") (pinfunction "1_1") (pintype "passive"))
      (node (ref "R2") (pin "1") (pinfunction "1_1") (pintype "passive"))
      (node (ref "U3") (pin "AA16") (pinfunction "_VDDQ_AA16") (pintype "power_in"))
      (node (ref "U3") (pin "AA3") (pinfunction "_VDDQ_AA3") (pintype "power_in"))
      (node (ref "U3") (pin "L18") (pinfunction "VDDQ_L18") (pintype "power_in"))
      (node (ref "U3") (pin "L2") (pinfunction "VDDQ_L2") (pintype "power_in"))
      (node (ref "U3") (pin "T18") (pinfunction "VDDQ_T18") (pintype "power_in"))
      (node (ref "U3") (pin "T2") (pinfunction "_VDDQ_T2") (pintype "power_in"))
      (node (ref "U3") (pin "V18") (pinfunction "VDDQ_V18") (pintype "power_in"))
      (node (ref "U3") (pin "V2") (pinfunction "_VDDQ_V2") (pintype "power_in"))
    )
    (net (code "74") (name "unconnected-(U1A-DRAM_AC03{slash}CS1_A_{slash}_C0_{slash}_---PadP2)") (class "Default")
      (node (ref "U1") (pin "P2") (pinfunction "DRAM_AC03/CS1_A_/_C0_/_--_P2") (pintype "passive"))
    )
    (net (code "75") (name "unconnected-(U1A-DRAM_AC20{slash}CKE0_B_{slash}_CK_t_B_{slash}_CK_B-PadT1)") (class "Default")
      (node (ref "U1") (pin "T1") (pinfunction "DRAM_AC20/CKE0_B_/_CK_t_B_/_CK_B_T1") (pintype "passive"))
    )
    (net (code "76") (name "unconnected-(U1A-DRAM_AC21{slash}CKE1_B_{slash}_CK_c_B_{slash}_CK#_B-PadT2)") (class "Default")
      (node (ref "U1") (pin "T2") (pinfunction "DRAM_AC21/CKE1_B_/_CK_c_B_/_CK#_B_T2") (pintype "passive"))
    )
    (net (code "77") (name "unconnected-(U1A-DRAM_AC23{slash}CS0_B_{slash}_--_{slash}_---PadR4)") (class "Default")
      (node (ref "U1") (pin "R4") (pinfunction "DRAM_AC23/CS0_B_/_--_/_--_R4") (pintype "passive"))
    )
    (net (code "78") (name "unconnected-(U1A-DRAM_AC32{slash}CA4_B_{slash}_C2_{slash}_---PadR5)") (class "Default")
      (node (ref "U1") (pin "R5") (pinfunction "DRAM_AC32/CA4_B_/_C2_/_--_R5") (pintype "passive"))
    )
    (net (code "79") (name "unconnected-(U1A-DRAM_ALERT_N-PadN5)") (class "Default")
      (node (ref "U1") (pin "N5") (pinfunction "DRAM_ALERT_N_N5") (pintype "passive"))
    )
    (net (code "80") (name "unconnected-(U3A-_CS1_A-PadAA11)") (class "Default")
      (node (ref "U3") (pin "AA11") (pinfunction "_CS1_A_AA11") (pintype "passive"))
    )
    (net (code "81") (name "unconnected-(U3A-_ODT(ca)_A-PadAA14)") (class "Default")
      (node (ref "U3") (pin "AA14") (pinfunction "_ODT(ca)_A_AA14") (pintype "passive"))
    )
    (net (code "82") (name "unconnected-(U3A-_VSF1-PadD1)") (class "Default")
      (node (ref "U3") (pin "D1") (pinfunction "_VSF1_D1") (pintype "passive"))
    )
    (net (code "83") (name "unconnected-(U3A-_VSF2-PadE1)") (class "Default")
      (node (ref "U3") (pin "E1") (pinfunction "_VSF2_E1") (pintype "passive"))
    )
    (net (code "84") (name "unconnected-(U3A-_VSF3-PadD2)") (class "Default")
      (node (ref "U3") (pin "D2") (pinfunction "_VSF3_D2") (pintype "passive"))
    )
    (net (code "85") (name "unconnected-(U3C-NC-PadA19)") (class "Default")
      (node (ref "U3") (pin "A19") (pinfunction "NC_A19") (pintype "passive"))
    )
    (net (code "86") (name "unconnected-(U3C-NC-PadAA19)") (class "Default")
      (node (ref "U3") (pin "AA19") (pinfunction "NC_AA19") (pintype "passive"))
    )
    (net (code "87") (name "unconnected-(U3C-NC-PadD18)") (class "Default")
      (node (ref "U3") (pin "D18") (pinfunction "NC_D18") (pintype "passive"))
    )
    (net (code "88") (name "unconnected-(U3C-NC-PadD19)") (class "Default")
      (node (ref "U3") (pin "D19") (pinfunction "NC_D19") (pintype "passive"))
    )
    (net (code "89") (name "unconnected-(U3C-NC-PadE2)") (class "Default")
      (node (ref "U3") (pin "E2") (pinfunction "NC_E2") (pintype "passive"))
    )
    (net (code "90") (name "unconnected-(U3C-NC-PadE18)") (class "Default")
      (node (ref "U3") (pin "E18") (pinfunction "NC_E18") (pintype "passive"))
    )
    (net (code "91") (name "unconnected-(U3C-NC-PadE19)") (class "Default")
      (node (ref "U3") (pin "E19") (pinfunction "NC_E19") (pintype "passive"))
    )
    (net (code "92") (name "unconnected-(U3C-NC-PadF18)") (class "Default")
      (node (ref "U3") (pin "F18") (pinfunction "NC_F18") (pintype "passive"))
    )
    (net (code "93") (name "unconnected-(U3C-NC-PadF19)") (class "Default")
      (node (ref "U3") (pin "F19") (pinfunction "NC_F19") (pintype "passive"))
    )
    (net (code "94") (name "unconnected-(U3C-NC-PadG18)") (class "Default")
      (node (ref "U3") (pin "G18") (pinfunction "NC_G18") (pintype "passive"))
    )
    (net (code "95") (name "unconnected-(U3C-NC-PadG19)") (class "Default")
      (node (ref "U3") (pin "G19") (pinfunction "NC_G19") (pintype "passive"))
    )
    (net (code "96") (name "unconnected-(U3C-_NC-PadA1)") (class "Default")
      (node (ref "U3") (pin "A1") (pinfunction "_NC_A1") (pintype "passive"))
    )
    (net (code "97") (name "unconnected-(U3C-_NC-PadAA1)") (class "Default")
      (node (ref "U3") (pin "AA1") (pinfunction "_NC_AA1") (pintype "passive"))
    )
  )
)
